# CPU.net
KiCad netlist of a schematic drawn in Altium Designer
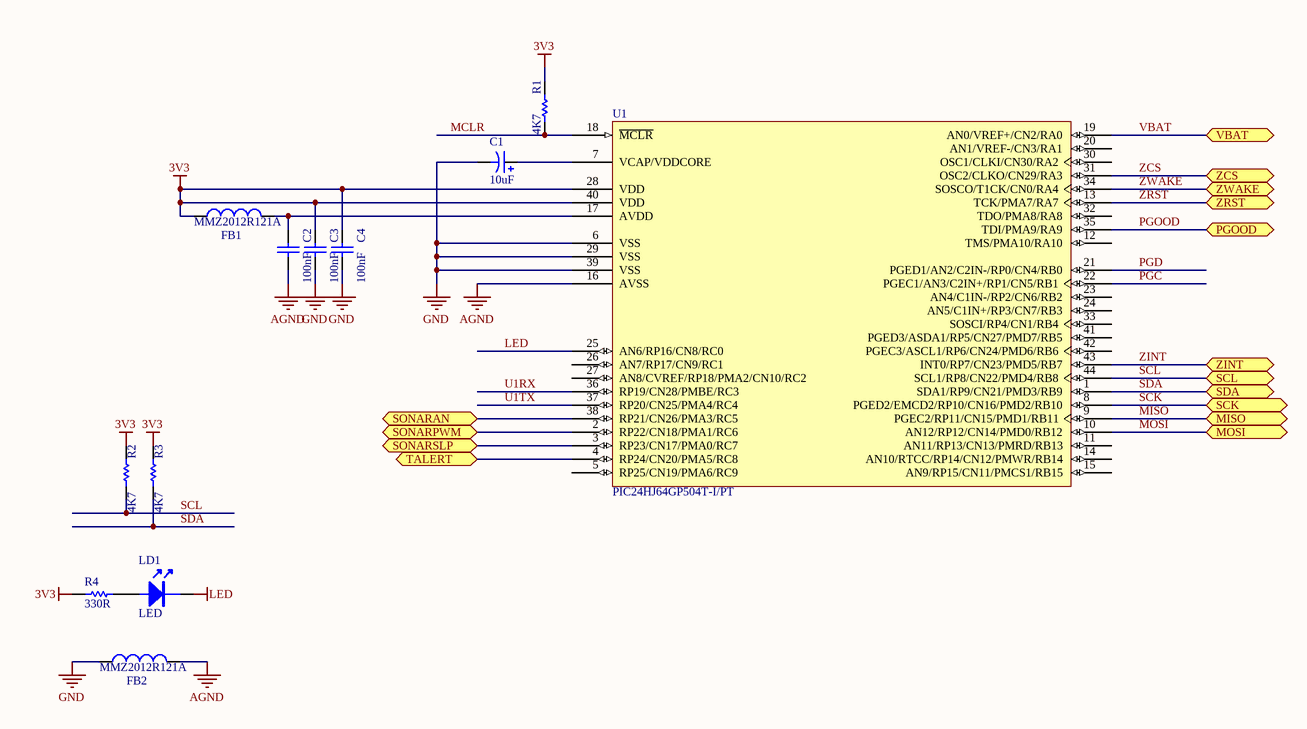
[diagram p0: CPU.SchDoc]

(export (version "E")
  (design (tool "Eeschema 10.0.6"))
  (components
    (comp (ref "C1")
      (value "10uF")
      (footprint "B")
      (description "Polarized Capacitor (Surface Mount)")
      (fields (field (name "Comment") "Cap Pol3") (field (name "PUBLISHER") "Altium Limited"))
      (libsource (lib "Miscellaneous Devices") (part "Cap Pol3"))
    )
    (comp (ref "C2")
      (value "100nF")
      (footprint "RESC2012L")
      (description "Capacitor (Semiconductor SIM Model)")
      (fields (field (name "Comment") "CAP0603-") (field (name "PUBLISHER") "Altium Limited"))
      (libsource (lib "Miscellaneous Devices") (part "Cap Semi"))
    )
    (comp (ref "C3")
      (value "100nF")
      (footprint "RESC2012L")
      (description "Capacitor (Semiconductor SIM Model)")
      (fields (field (name "Comment") "CAP0603-") (field (name "PUBLISHER") "Altium Limited"))
      (libsource (lib "Miscellaneous Devices") (part "Cap Semi"))
    )
    (comp (ref "C4")
      (value "100nF")
      (footprint "RESC2012L")
      (description "Capacitor (Semiconductor SIM Model)")
      (fields (field (name "Comment") "CAP0603-") (field (name "PUBLISHER") "Altium Limited"))
      (libsource (lib "Miscellaneous Devices") (part "Cap Semi"))
    )
    (comp (ref "FB1")
      (value "MMZ2012R121A")
      (footprint "RESC2012L")
      (description "Inductor")
      (fields (field (name "PUBLISHER") "Altium Limited"))
      (libsource (lib "Miscellaneous Devices") (part "Inductor"))
    )
    (comp (ref "FB2")
      (value "MMZ2012R121A")
      (footprint "RESC2012L")
      (description "Inductor")
      (fields (field (name "PUBLISHER") "Altium Limited"))
      (libsource (lib "Miscellaneous Devices") (part "Inductor"))
    )
    (comp (ref "LD1") (value "LED") (footprint "LED805") (libsource (lib "DCT_SCH") (part "LED")))
    (comp (ref "R1")
      (value "4K7")
      (footprint "RESC2012L")
      (description "Semiconductor Resistor")
      (fields (field (name "Comment") "RES0603-") (field (name "PUBLISHER") "Altium Limited"))
      (libsource (lib "Miscellaneous Devices") (part "Res Semi"))
    )
    (comp (ref "R2")
      (value "4K7")
      (footprint "RESC2012L")
      (description "Semiconductor Resistor")
      (fields (field (name "Comment") "RES0603-") (field (name "PUBLISHER") "Altium Limited"))
      (libsource (lib "Miscellaneous Devices") (part "Res Semi"))
    )
    (comp (ref "R3")
      (value "4K7")
      (footprint "RESC2012L")
      (description "Semiconductor Resistor")
      (fields (field (name "Comment") "RES0603-") (field (name "PUBLISHER") "Altium Limited"))
      (libsource (lib "Miscellaneous Devices") (part "Res Semi"))
    )
    (comp (ref "R4")
      (value "330R")
      (footprint "RESC2012L")
      (description "Semiconductor Resistor")
      (fields (field (name "Comment") "RES0603-") (field (name "PUBLISHER") "Altium Limited"))
      (libsource (lib "Miscellaneous Devices") (part "Res Semi"))
    )
    (comp (ref "U1")
      (value "PIC24HJ64GP504T-I/PT")
      (footprint "TQFP-PT44_M")
      (fields (field (name "PUBLISHER") "Altium Limited"))
      (libsource (lib "Microchip Microcontroller 16-Bit PIC24H") (part "PIC24HJ64GP504T-I/PT"))
    )
  )
  (nets
    (net (code "1") (name "/MCLR") (class "Default")
      (node (ref "R1") (pin "1") (pinfunction "1_1") (pintype "passive"))
      (node (ref "U1") (pin "18") (pinfunction "~{MCLR}_18") (pintype "input"))
    )
    (net (code "2") (name "/MISO") (class "Default")
      (node (ref "U1") (pin "9") (pinfunction "PGEC2/RP11/CN15/PMD1/RB11_9") (pintype "bidirectional"))
    )
    (net (code "3") (name "/MOSI") (class "Default")
      (node (ref "U1") (pin "10") (pinfunction "AN12/RP12/CN14/PMD0/RB12_10") (pintype "bidirectional"))
    )
    (net (code "4") (name "/PGC") (class "Default")
      (node (ref "U1") (pin "22") (pinfunction "PGEC1/AN3/C2IN+/RP1/CN5/RB1_22") (pintype "bidirectional"))
    )
    (net (code "5") (name "/PGD") (class "Default")
      (node (ref "U1") (pin "21") (pinfunction "PGED1/AN2/C2IN-/RP0/CN4/RB0_21") (pintype "bidirectional"))
    )
    (net (code "6") (name "/PGOOD") (class "Default")
      (node (ref "U1") (pin "35") (pinfunction "TDI/PMA9/RA9_35") (pintype "bidirectional"))
    )
    (net (code "7") (name "/SCK") (class "Default")
      (node (ref "U1") (pin "8") (pinfunction "PGED2/EMCD2/RP10/CN16/PMD2/RB10_8") (pintype "bidirectional"))
    )
    (net (code "8") (name "/SCL") (class "Default")
      (node (ref "R2") (pin "1") (pinfunction "1_1") (pintype "passive"))
      (node (ref "U1") (pin "44") (pinfunction "SCL1/RP8/CN22/PMD4/RB8_44") (pintype "bidirectional"))
    )
    (net (code "9") (name "/SDA") (class "Default")
      (node (ref "R3") (pin "1") (pinfunction "1_1") (pintype "passive"))
      (node (ref "U1") (pin "1") (pinfunction "SDA1/RP9/CN21/PMD3/RB9_1") (pintype "bidirectional"))
    )
    (net (code "10") (name "/SONARAN") (class "Default")
      (node (ref "U1") (pin "38") (pinfunction "RP21/CN26/PMA3/RC5_38") (pintype "bidirectional"))
    )
    (net (code "11") (name "/SONARPWM") (class "Default")
      (node (ref "U1") (pin "2") (pinfunction "RP22/CN18/PMA1/RC6_2") (pintype "bidirectional"))
    )
    (net (code "12") (name "/SONARSLP") (class "Default")
      (node (ref "U1") (pin "3") (pinfunction "RP23/CN17/PMA0/RC7_3") (pintype "bidirectional"))
    )
    (net (code "13") (name "/TALERT") (class "Default")
      (node (ref "U1") (pin "4") (pinfunction "RP24/CN20/PMA5/RC8_4") (pintype "bidirectional"))
    )
    (net (code "14") (name "/U1RX") (class "Default")
      (node (ref "U1") (pin "36") (pinfunction "RP19/CN28/PMBE/RC3_36") (pintype "bidirectional"))
    )
    (net (code "15") (name "/U1TX") (class "Default")
      (node (ref "U1") (pin "37") (pinfunction "RP20/CN25/PMA4/RC4_37") (pintype "bidirectional"))
    )
    (net (code "16") (name "/VBAT") (class "Default")
      (node (ref "U1") (pin "19") (pinfunction "AN0/VREF+/CN2/RA0_19") (pintype "bidirectional"))
    )
    (net (code "17") (name "/ZCS") (class "Default")
      (node (ref "U1") (pin "31") (pinfunction "OSC2/CLKO/CN29/RA3_31") (pintype "bidirectional"))
    )
    (net (code "18") (name "/ZINT") (class "Default")
      (node (ref "U1") (pin "43") (pinfunction "INT0/RP7/CN23/PMD5/RB7_43") (pintype "bidirectional"))
    )
    (net (code "19") (name "/ZRST") (class "Default")
      (node (ref "U1") (pin "13") (pinfunction "TCK/PMA7/RA7_13") (pintype "bidirectional"))
    )
    (net (code "20") (name "/ZWAKE") (class "Default")
      (node (ref "U1") (pin "34") (pinfunction "SOSCO/T1CK/CN0/RA4_34") (pintype "bidirectional"))
    )
    (net (code "21") (name "3V3") (class "Default")
      (node (ref "C3") (pin "2") (pinfunction "2_2") (pintype "passive"))
      (node (ref "C4") (pin "2") (pinfunction "2_2") (pintype "passive"))
      (node (ref "FB1") (pin "1") (pinfunction "1_1") (pintype "passive"))
      (node (ref "R1") (pin "2") (pinfunction "2_2") (pintype "passive"))
      (node (ref "R2") (pin "2") (pinfunction "2_2") (pintype "passive"))
      (node (ref "R3") (pin "2") (pinfunction "2_2") (pintype "passive"))
      (node (ref "R4") (pin "2") (pinfunction "2_2") (pintype "passive"))
      (node (ref "U1") (pin "28") (pinfunction "VDD_28") (pintype "power_in"))
      (node (ref "U1") (pin "40") (pinfunction "VDD_40") (pintype "power_in"))
    )
    (net (code "22") (name "AGND") (class "Default")
      (node (ref "C2") (pin "1") (pinfunction "1_1") (pintype "passive"))
      (node (ref "FB2") (pin "2") (pinfunction "2_2") (pintype "passive"))
      (node (ref "U1") (pin "16") (pinfunction "AVSS_16") (pintype "power_in"))
    )
    (net (code "23") (name "GND") (class "Default")
      (node (ref "C1") (pin "2") (pinfunction "2_2") (pintype "passive"))
      (node (ref "C3") (pin "1") (pinfunction "1_1") (pintype "passive"))
      (node (ref "C4") (pin "1") (pinfunction "1_1") (pintype "passive"))
      (node (ref "FB2") (pin "1") (pinfunction "1_1") (pintype "passive"))
      (node (ref "U1") (pin "29") (pinfunction "VSS_29") (pintype "power_in"))
      (node (ref "U1") (pin "39") (pinfunction "VSS_39") (pintype "power_in"))
      (node (ref "U1") (pin "6") (pinfunction "VSS_6") (pintype "power_in"))
    )
    (net (code "24") (name "LED") (class "Default")
      (node (ref "LD1") (pin "K") (pintype "passive"))
      (node (ref "U1") (pin "25") (pinfunction "AN6/RP16/CN8/RC0_25") (pintype "bidirectional"))
    )
    (net (code "25") (name "Net-(LD1-PadA)") (class "Default")
      (node (ref "LD1") (pin "A") (pintype "passive"))
      (node (ref "R4") (pin "1") (pinfunction "1_1") (pintype "passive"))
    )
    (net (code "26") (name "Net-(U1-AVDD)") (class "Default")
      (node (ref "C2") (pin "2") (pinfunction "2_2") (pintype "passive"))
      (node (ref "FB1") (pin "2") (pinfunction "2_2") (pintype "passive"))
      (node (ref "U1") (pin "17") (pinfunction "AVDD_17") (pintype "power_in"))
    )
    (net (code "27") (name "Net-(U1-VCAP{slash}VDDCORE)") (class "Default")
      (node (ref "C1") (pin "1") (pinfunction "1_1") (pintype "passive"))
      (node (ref "U1") (pin "7") (pinfunction "VCAP/VDDCORE_7") (pintype "power_in"))
    )
    (net (code "28") (name "unconnected-(U1-AN1{slash}VREF-{slash}CN3{slash}RA1-Pad20)") (class "Default")
      (node (ref "U1") (pin "20") (pinfunction "AN1/VREF-/CN3/RA1_20") (pintype "bidirectional"))
    )
    (net (code "29") (name "unconnected-(U1-AN4{slash}C1IN-{slash}RP2{slash}CN6{slash}RB2-Pad23)") (class "Default")
      (node (ref "U1") (pin "23") (pinfunction "AN4/C1IN-/RP2/CN6/RB2_23") (pintype "bidirectional"))
    )
    (net (code "30") (name "unconnected-(U1-AN5{slash}C1IN+{slash}RP3{slash}CN7{slash}RB3-Pad24)") (class "Default")
      (node (ref "U1") (pin "24") (pinfunction "AN5/C1IN+/RP3/CN7/RB3_24") (pintype "bidirectional"))
    )
    (net (code "31") (name "unconnected-(U1-AN7{slash}RP17{slash}CN9{slash}RC1-Pad26)") (class "Default")
      (node (ref "U1") (pin "26") (pinfunction "AN7/RP17/CN9/RC1_26") (pintype "bidirectional"))
    )
    (net (code "32") (name "unconnected-(U1-AN8{slash}CVREF{slash}RP18{slash}PMA2{slash}CN10{slash}RC2-Pad27)") (class "Default")
      (node (ref "U1") (pin "27") (pinfunction "AN8/CVREF/RP18/PMA2/CN10/RC2_27") (pintype "bidirectional"))
    )
    (net (code "33") (name "unconnected-(U1-AN9{slash}RP15{slash}CN11{slash}PMCS1{slash}RB15-Pad15)") (class "Default")
      (node (ref "U1") (pin "15") (pinfunction "AN9/RP15/CN11/PMCS1/RB15_15") (pintype "bidirectional"))
    )
    (net (code "34") (name "unconnected-(U1-AN10{slash}RTCC{slash}RP14{slash}CN12{slash}PMWR{slash}RB14-Pad14)") (class "Default")
      (node (ref "U1") (pin "14") (pinfunction "AN10/RTCC/RP14/CN12/PMWR/RB14_14") (pintype "bidirectional"))
    )
    (net (code "35") (name "unconnected-(U1-AN11{slash}RP13{slash}CN13{slash}PMRD{slash}RB13-Pad11)") (class "Default")
      (node (ref "U1") (pin "11") (pinfunction "AN11/RP13/CN13/PMRD/RB13_11") (pintype "bidirectional"))
    )
    (net (code "36") (name "unconnected-(U1-OSC1{slash}CLKI{slash}CN30{slash}RA2-Pad30)") (class "Default")
      (node (ref "U1") (pin "30") (pinfunction "OSC1/CLKI/CN30/RA2_30") (pintype "bidirectional"))
    )
    (net (code "37") (name "unconnected-(U1-PGEC3{slash}ASCL1{slash}RP6{slash}CN24{slash}PMD6{slash}RB6-Pad42)") (class "Default")
      (node (ref "U1") (pin "42") (pinfunction "PGEC3/ASCL1/RP6/CN24/PMD6/RB6_42") (pintype "bidirectional"))
    )
    (net (code "38") (name "unconnected-(U1-PGED3{slash}ASDA1{slash}RP5{slash}CN27{slash}PMD7{slash}RB5-Pad41)") (class "Default")
      (node (ref "U1") (pin "41") (pinfunction "PGED3/ASDA1/RP5/CN27/PMD7/RB5_41") (pintype "bidirectional"))
    )
    (net (code "39") (name "unconnected-(U1-RP25{slash}CN19{slash}PMA6{slash}RC9-Pad5)") (class "Default")
      (node (ref "U1") (pin "5") (pinfunction "RP25/CN19/PMA6/RC9_5") (pintype "bidirectional"))
    )
    (net (code "40") (name "unconnected-(U1-SOSCI{slash}RP4{slash}CN1{slash}RB4-Pad33)") (class "Default")
      (node (ref "U1") (pin "33") (pinfunction "SOSCI/RP4/CN1/RB4_33") (pintype "bidirectional"))
    )
    (net (code "41") (name "unconnected-(U1-TDO{slash}PMA8{slash}RA8-Pad32)") (class "Default")
      (node (ref "U1") (pin "32") (pinfunction "TDO/PMA8/RA8_32") (pintype "bidirectional"))
    )
    (net (code "42") (name "unconnected-(U1-TMS{slash}PMA10{slash}RA10-Pad12)") (class "Default")
      (node (ref "U1") (pin "12") (pinfunction "TMS/PMA10/RA10_12") (pintype "bidirectional"))
    )
  )
)
